# Slave.net
KiCad netlist of a schematic drawn in Altium Designer
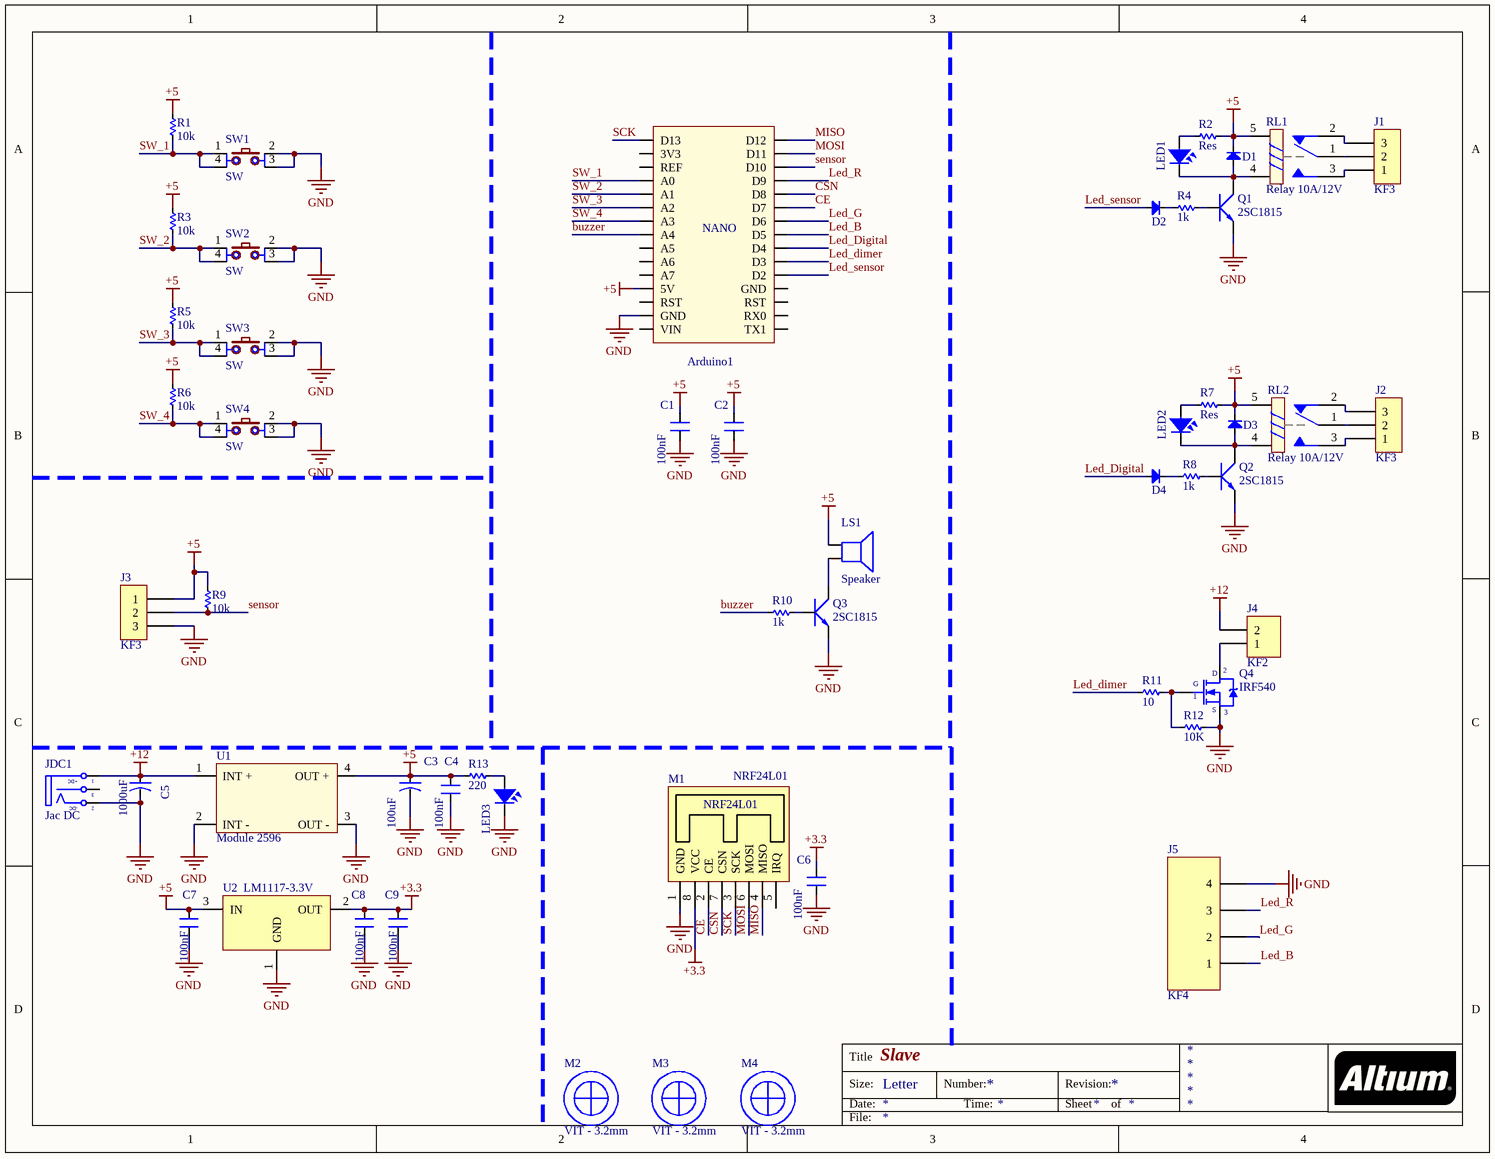
[diagram p0: Slave.SchDoc]

(export (version "E")
  (design (tool "Eeschema 10.0.6"))
  (components
    (comp (ref "Arduino1")
      (value "Arduino Nano")
      (footprint "Arduino Nano")
      (description "Arduino NANO")
      (libsource (lib "thu vien 3d") (part "Arduino Nano"))
    )
    (comp (ref "C1") (value "100nF") (footprint "CN1.5") (libsource (lib "thu vien 3d") (part "CN")))
    (comp (ref "C2") (value "100nF") (footprint "CN1.5") (libsource (lib "thu vien 3d") (part "CN")))
    (comp (ref "C3")
      (value "100uF")
      (footprint "CA-ALU-5")
      (description "Capacitor (Semiconductor SIM Model)")
      (fields (field (name "PUBLISHER") "Altium Limited"))
      (libsource (lib "thu vien 3d") (part "CN-ALU-DIP"))
    )
    (comp (ref "C4") (value "100nF") (footprint "CN1.5") (libsource (lib "thu vien 3d") (part "CN")))
    (comp (ref "C5")
      (value "1000uF")
      (footprint "CA-ALU-6.3")
      (description "Capacitor (Semiconductor SIM Model)")
      (fields (field (name "PUBLISHER") "Altium Limited"))
      (libsource (lib "thu vien 3d") (part "CN-ALU-DIP"))
    )
    (comp (ref "C6") (value "100nF") (footprint "CN1.5") (libsource (lib "thu vien 3d") (part "CN")))
    (comp (ref "C7") (value "100nF") (footprint "CN-SMD-0603") (libsource (lib "thu vien 3d") (part "CN")))
    (comp (ref "C8") (value "100nF") (footprint "CN-SMD-0603") (libsource (lib "thu vien 3d") (part "CN")))
    (comp (ref "C9") (value "100nF") (footprint "CN-SMD-0603") (libsource (lib "thu vien 3d") (part "CN")))
    (comp (ref "D1")
      (value "Diode")
      (footprint "DIO-1A")
      (description "Default Diode")
      (fields (field (name "PUBLISHER") "Altium Limited"))
      (libsource (lib "thu vien 3d") (part "Diode"))
    )
    (comp (ref "D2")
      (value "Diode")
      (footprint "DIO-1A")
      (description "Default Diode")
      (fields (field (name "PUBLISHER") "Altium Limited"))
      (libsource (lib "thu vien 3d") (part "Diode"))
    )
    (comp (ref "D3")
      (value "Diode")
      (footprint "DIO-1A")
      (description "Default Diode")
      (fields (field (name "PUBLISHER") "Altium Limited"))
      (libsource (lib "thu vien 3d") (part "Diode"))
    )
    (comp (ref "D4")
      (value "Diode")
      (footprint "DIO-1A")
      (description "Default Diode")
      (fields (field (name "PUBLISHER") "Altium Limited"))
      (libsource (lib "thu vien 3d") (part "Diode"))
    )
    (comp (ref "J1")
      (value "KF3")
      (footprint "KF3-5.08")
      (fields
        (field (name "MANUFACTURER") "Würth Elektronik eiSos GmbH")
        (field (name "PARTNO") "691103110003")
        (field (name "CREATED BY") "Karrer Zheng")
      )
      (libsource (lib "thu vien 3d") (part "KF3"))
    )
    (comp (ref "J2")
      (value "KF3")
      (footprint "KF3-5.08")
      (fields
        (field (name "MANUFACTURER") "Würth Elektronik eiSos GmbH")
        (field (name "PARTNO") "691103110003")
        (field (name "CREATED BY") "Karrer Zheng")
      )
      (libsource (lib "thu vien 3d") (part "KF3"))
    )
    (comp (ref "J3")
      (value "KF3")
      (footprint "KF3-5.08")
      (fields
        (field (name "MANUFACTURER") "Würth Elektronik eiSos GmbH")
        (field (name "PARTNO") "691103110003")
        (field (name "CREATED BY") "Karrer Zheng")
      )
      (libsource (lib "") (part "KF3_1"))
    )
    (comp (ref "J4")
      (value "KF2")
      (footprint "KF2-5.08")
      (fields
        (field (name "MANUFACTURER") "Würth Elektronik eiSos GmbH")
        (field (name "PARTNO") "691103110002")
        (field (name "CREATED BY") "Karrer Zheng")
      )
      (libsource (lib "thu vien 3d") (part "KF2"))
    )
    (comp (ref "J5")
      (value "KF4")
      (footprint "KF4-5.08")
      (fields
        (field (name "MANUFACTURER") "Würth Elektronik eiSos GmbH")
        (field (name "PARTNO") "691133710004")
        (field (name "CREATED BY") "Baojun Chen")
      )
      (libsource (lib "thu vien 3d") (part "KF4"))
    )
    (comp (ref "JDC1")
      (value "Jac DC")
      (footprint "DC0")
      (description "Jac DC input")
      (libsource (lib "thu vien 3d") (part "DCIN"))
    )
    (comp (ref "LED1")
      (value "LED")
      (footprint "LED-5-Green")
      (description "LED Single colour Green and Red")
      (libsource (lib "thu vien 3d") (part "LED"))
    )
    (comp (ref "LED2")
      (value "LED")
      (footprint "LED-5-Green")
      (description "LED Single colour Green and Red")
      (libsource (lib "thu vien 3d") (part "LED"))
    )
    (comp (ref "LED3")
      (value "LED")
      (footprint "LED-3MM-RED")
      (description "LED Single colour Green and Red")
      (libsource (lib "thu vien 3d") (part "LED"))
    )
    (comp (ref "LS1")
      (value "Speaker")
      (footprint "SPEAKER")
      (description "Loudspeaker")
      (fields (field (name "PUBLISHER") "Altium Limited"))
      (libsource (lib "thu vien 3d") (part "Speaker"))
    )
    (comp (ref "M1")
      (value "NRF24L01")
      (footprint "NRF24L01")
      (libsource (lib "thu vien 3d") (part "NRF24L01"))
    )
    (comp (ref "M2")
      (value "VIT - 3.2mm")
      (footprint "VIT - 3.2MM_2")
      (libsource (lib "Nichietsuvn") (part "VIT - 3.2mm"))
    )
    (comp (ref "M3")
      (value "VIT - 3.2mm")
      (footprint "VIT - 3.2MM_2")
      (libsource (lib "Nichietsuvn") (part "VIT - 3.2mm"))
    )
    (comp (ref "M4")
      (value "VIT - 3.2mm")
      (footprint "VIT - 3.2MM_2")
      (libsource (lib "Nichietsuvn") (part "VIT - 3.2mm"))
    )
    (comp (ref "Q1")
      (value "2SC1815")
      (footprint "TO92-123")
      (description "NPN 600mW, ECB")
      (libsource (lib "thu vien 3d") (part "2SC1815"))
    )
    (comp (ref "Q2")
      (value "2SC1815")
      (footprint "TO92-123")
      (description "NPN 600mW, ECB")
      (libsource (lib "thu vien 3d") (part "2SC1815"))
    )
    (comp (ref "Q3")
      (value "2SC1815")
      (footprint "TO92-123")
      (description "NPN 600mW, ECB")
      (libsource (lib "thu vien 3d") (part "2SC1815"))
    )
    (comp (ref "Q4")
      (value "IRF540")
      (footprint "TO220-123")
      (description "MOSFET N - CHANNEL 500V - 0.75 - 8A - TO-220")
      (libsource (lib "thu vien 3d") (part "IRF840"))
    )
    (comp (ref "R1")
      (value "10k")
      (footprint "RES-1/4W")
      (description "Res")
      (fields
        (field (name "MANUFACTURER") "Generic Components")
        (field (name "PUBLISHER") "Altium Hobart Technology Centre")
      )
      (libsource (lib "thu vien 3d") (part "Res"))
    )
    (comp (ref "R2")
      (value "Res")
      (footprint "RES-1/4W-SMALL")
      (fields
        (field (name "MANUFACTURER") "Generic Components")
        (field (name "PUBLISHER") "Altium Hobart Technology Centre")
      )
      (libsource (lib "thu vien 3d") (part "Res"))
    )
    (comp (ref "R3")
      (value "10k")
      (footprint "RES-1/4W")
      (description "Res")
      (fields
        (field (name "MANUFACTURER") "Generic Components")
        (field (name "PUBLISHER") "Altium Hobart Technology Centre")
      )
      (libsource (lib "thu vien 3d") (part "Res"))
    )
    (comp (ref "R4")
      (value "1k")
      (footprint "RES-1/4W-SMALL")
      (description "Res")
      (fields
        (field (name "MANUFACTURER") "Generic Components")
        (field (name "PUBLISHER") "Altium Hobart Technology Centre")
      )
      (libsource (lib "thu vien 3d") (part "Res"))
    )
    (comp (ref "R5")
      (value "10k")
      (footprint "RES-1/4W")
      (description "Res")
      (fields
        (field (name "MANUFACTURER") "Generic Components")
        (field (name "PUBLISHER") "Altium Hobart Technology Centre")
      )
      (libsource (lib "thu vien 3d") (part "Res"))
    )
    (comp (ref "R6")
      (value "10k")
      (footprint "RES-1/4W")
      (description "Res")
      (fields
        (field (name "MANUFACTURER") "Generic Components")
        (field (name "PUBLISHER") "Altium Hobart Technology Centre")
      )
      (libsource (lib "thu vien 3d") (part "Res"))
    )
    (comp (ref "R7")
      (value "Res")
      (footprint "RES-1/4W-SMALL")
      (fields
        (field (name "MANUFACTURER") "Generic Components")
        (field (name "PUBLISHER") "Altium Hobart Technology Centre")
      )
      (libsource (lib "thu vien 3d") (part "Res"))
    )
    (comp (ref "R8")
      (value "1k")
      (footprint "RES-1/4W-SMALL")
      (description "Res")
      (fields
        (field (name "MANUFACTURER") "Generic Components")
        (field (name "PUBLISHER") "Altium Hobart Technology Centre")
      )
      (libsource (lib "thu vien 3d") (part "Res"))
    )
    (comp (ref "R9")
      (value "10k")
      (footprint "RES-1/4W")
      (description "Res")
      (fields
        (field (name "MANUFACTURER") "Generic Components")
        (field (name "PUBLISHER") "Altium Hobart Technology Centre")
      )
      (libsource (lib "thu vien 3d") (part "Res"))
    )
    (comp (ref "R10")
      (value "1k")
      (footprint "RES-1/4W-SMALL")
      (description "Res")
      (fields
        (field (name "MANUFACTURER") "Generic Components")
        (field (name "PUBLISHER") "Altium Hobart Technology Centre")
      )
      (libsource (lib "thu vien 3d") (part "Res"))
    )
    (comp (ref "R11")
      (value "10")
      (footprint "RES-1/4W-SMALL")
      (description "Res")
      (fields
        (field (name "MANUFACTURER") "Generic Components")
        (field (name "PUBLISHER") "Altium Hobart Technology Centre")
      )
      (libsource (lib "thu vien 3d") (part "Res"))
    )
    (comp (ref "R12")
      (value "10K")
      (footprint "RES-1/4W-SMALL")
      (description "Res")
      (fields
        (field (name "MANUFACTURER") "Generic Components")
        (field (name "PUBLISHER") "Altium Hobart Technology Centre")
      )
      (libsource (lib "thu vien 3d") (part "Res"))
    )
    (comp (ref "R13")
      (value "220")
      (footprint "RES-1/4WD")
      (description "Res")
      (fields
        (field (name "MANUFACTURER") "Generic Components")
        (field (name "PUBLISHER") "Altium Hobart Technology Centre")
      )
      (libsource (lib "thu vien 3d") (part "Res"))
    )
    (comp (ref "RL1")
      (value "Relay 10A/12V")
      (footprint "RELAY 5")
      (description "Relay SPDT,10A - 12VDC 5 Pin")
      (libsource (lib "thu vien 3d") (part "Relay 5"))
    )
    (comp (ref "RL2")
      (value "Relay 10A/12V")
      (footprint "RELAY 5")
      (description "Relay SPDT,10A - 12VDC 5 Pin")
      (libsource (lib "thu vien 3d") (part "Relay 5"))
    )
    (comp (ref "SW1")
      (value "SW")
      (footprint "SW2-DIP")
      (description "Switch button 4 pin")
      (libsource (lib "thu vien 3d") (part "SW4"))
    )
    (comp (ref "SW2")
      (value "SW")
      (footprint "SW2-DIP")
      (description "Switch button 4 pin")
      (libsource (lib "thu vien 3d") (part "SW4"))
    )
    (comp (ref "SW3")
      (value "SW")
      (footprint "SW2-DIP")
      (description "Switch button 4 pin")
      (libsource (lib "thu vien 3d") (part "SW4"))
    )
    (comp (ref "SW4")
      (value "SW")
      (footprint "SW2-DIP")
      (description "Switch button 4 pin")
      (libsource (lib "thu vien 3d") (part "SW4"))
    )
    (comp (ref "U1")
      (value "Module 2596")
      (footprint "Module 2596")
      (libsource (lib "Nichietsuvn") (part "Module 2596"))
    )
    (comp (ref "U2")
      (value "LM1117-3.3V")
      (footprint "SOT223")
      (description "800mA Low-Dropout Linear Regulator")
      (fields (field (name "CREATOR") "Nguyen Ba Bien"))
      (libsource (lib "thu vien 3d") (part "LM1117"))
    )
  )
  (nets
    (net (code "1") (name "+3.3") (class "Default")
      (node (ref "C6") (pin "2") (pinfunction "2_2") (pintype "passive"))
      (node (ref "C8") (pin "2") (pinfunction "2_2") (pintype "passive"))
      (node (ref "C9") (pin "2") (pinfunction "2_2") (pintype "passive"))
      (node (ref "M1") (pin "8") (pinfunction "VCC_8") (pintype "passive"))
      (node (ref "U2") (pin "2") (pinfunction "OUT_2") (pintype "passive"))
    )
    (net (code "2") (name "+5") (class "Default")
      (node (ref "Arduino1") (pin "5V") (pinfunction "5V_5V") (pintype "passive"))
      (node (ref "C1") (pin "2") (pinfunction "2_2") (pintype "passive"))
      (node (ref "C2") (pin "2") (pinfunction "2_2") (pintype "passive"))
      (node (ref "C3") (pin "1") (pinfunction "1_1") (pintype "passive"))
      (node (ref "C4") (pin "2") (pinfunction "2_2") (pintype "passive"))
      (node (ref "C7") (pin "2") (pinfunction "2_2") (pintype "passive"))
      (node (ref "D1") (pin "2") (pinfunction "K_2") (pintype "passive"))
      (node (ref "D3") (pin "2") (pinfunction "K_2") (pintype "passive"))
      (node (ref "J3") (pin "1") (pinfunction "1_1") (pintype "passive"))
      (node (ref "LS1") (pin "1") (pinfunction "1_1") (pintype "passive"))
      (node (ref "R1") (pin "1") (pinfunction "1_1") (pintype "passive"))
      (node (ref "R13") (pin "2") (pinfunction "2_2") (pintype "passive"))
      (node (ref "R2") (pin "1") (pinfunction "1_1") (pintype "passive"))
      (node (ref "R3") (pin "1") (pinfunction "1_1") (pintype "passive"))
      (node (ref "R5") (pin "1") (pinfunction "1_1") (pintype "passive"))
      (node (ref "R6") (pin "1") (pinfunction "1_1") (pintype "passive"))
      (node (ref "R7") (pin "1") (pinfunction "1_1") (pintype "passive"))
      (node (ref "R9") (pin "1") (pinfunction "1_1") (pintype "passive"))
      (node (ref "RL1") (pin "5") (pinfunction "5_5") (pintype "passive"))
      (node (ref "RL2") (pin "5") (pinfunction "5_5") (pintype "passive"))
      (node (ref "U1") (pin "4") (pinfunction "OUT_+_4") (pintype "passive"))
      (node (ref "U2") (pin "3") (pinfunction "IN_3") (pintype "passive"))
    )
    (net (code "3") (name "+12") (class "Default")
      (node (ref "C5") (pin "1") (pinfunction "1_1") (pintype "passive"))
      (node (ref "J4") (pin "2") (pinfunction "2_2") (pintype "passive"))
      (node (ref "JDC1") (pin "1") (pinfunction "T_1") (pintype "passive"))
      (node (ref "U1") (pin "1") (pinfunction "INT_+_1") (pintype "passive"))
    )
    (net (code "4") (name "/CE") (class "Default")
      (node (ref "Arduino1") (pin "D7") (pinfunction "D7_D7") (pintype "passive"))
      (node (ref "M1") (pin "2") (pinfunction "CE_2") (pintype "passive"))
    )
    (net (code "5") (name "/CSN") (class "Default")
      (node (ref "Arduino1") (pin "D8") (pinfunction "D8_D8") (pintype "passive"))
      (node (ref "M1") (pin "7") (pinfunction "CSN_7") (pintype "passive"))
    )
    (net (code "6") (name "/Led_B") (class "Default")
      (node (ref "Arduino1") (pin "D5") (pinfunction "D5_D5") (pintype "passive"))
      (node (ref "J5") (pin "1") (pinfunction "1_1") (pintype "passive"))
    )
    (net (code "7") (name "/Led_Digital") (class "Default")
      (node (ref "Arduino1") (pin "D4") (pinfunction "D4_D4") (pintype "passive"))
      (node (ref "D4") (pin "1") (pinfunction "A_1") (pintype "passive"))
    )
    (net (code "8") (name "/Led_G") (class "Default")
      (node (ref "Arduino1") (pin "D6") (pinfunction "D6_D6") (pintype "passive"))
      (node (ref "J5") (pin "2") (pinfunction "2_2") (pintype "passive"))
    )
    (net (code "9") (name "/Led_R") (class "Default")
      (node (ref "Arduino1") (pin "D9") (pinfunction "D9_D9") (pintype "passive"))
      (node (ref "J5") (pin "3") (pinfunction "3_3") (pintype "passive"))
    )
    (net (code "10") (name "/Led_dimer") (class "Default")
      (node (ref "Arduino1") (pin "D3") (pinfunction "D3_D3") (pintype "passive"))
      (node (ref "R11") (pin "2") (pinfunction "2_2") (pintype "passive"))
    )
    (net (code "11") (name "/Led_sensor") (class "Default")
      (node (ref "Arduino1") (pin "D2") (pinfunction "D2_D2") (pintype "passive"))
      (node (ref "D2") (pin "1") (pinfunction "A_1") (pintype "passive"))
    )
    (net (code "12") (name "/MISO") (class "Default")
      (node (ref "Arduino1") (pin "D12") (pinfunction "D12_D12") (pintype "passive"))
      (node (ref "M1") (pin "4") (pinfunction "MISO_4") (pintype "passive"))
    )
    (net (code "13") (name "/MOSI") (class "Default")
      (node (ref "Arduino1") (pin "D11") (pinfunction "D11_D11") (pintype "passive"))
      (node (ref "M1") (pin "6") (pinfunction "MOSI_6") (pintype "passive"))
    )
    (net (code "14") (name "/SCK") (class "Default")
      (node (ref "Arduino1") (pin "D13") (pinfunction "D13_D13") (pintype "passive"))
      (node (ref "M1") (pin "3") (pinfunction "SCK_3") (pintype "passive"))
    )
    (net (code "15") (name "/SW_1") (class "Default")
      (node (ref "Arduino1") (pin "A0") (pinfunction "A0_A0") (pintype "passive"))
      (node (ref "R1") (pin "2") (pinfunction "2_2") (pintype "passive"))
      (node (ref "SW1") (pin "1") (pintype "passive"))
      (node (ref "SW1") (pin "4") (pinfunction "4_4") (pintype "passive"))
    )
    (net (code "16") (name "/SW_2") (class "Default")
      (node (ref "Arduino1") (pin "A1") (pinfunction "A1_A1") (pintype "passive"))
      (node (ref "R3") (pin "2") (pinfunction "2_2") (pintype "passive"))
      (node (ref "SW2") (pin "1") (pintype "passive"))
      (node (ref "SW2") (pin "4") (pinfunction "4_4") (pintype "passive"))
    )
    (net (code "17") (name "/SW_3") (class "Default")
      (node (ref "Arduino1") (pin "A2") (pinfunction "A2_A2") (pintype "passive"))
      (node (ref "R5") (pin "2") (pinfunction "2_2") (pintype "passive"))
      (node (ref "SW3") (pin "1") (pintype "passive"))
      (node (ref "SW3") (pin "4") (pinfunction "4_4") (pintype "passive"))
    )
    (net (code "18") (name "/SW_4") (class "Default")
      (node (ref "Arduino1") (pin "A3") (pinfunction "A3_A3") (pintype "passive"))
      (node (ref "R6") (pin "2") (pinfunction "2_2") (pintype "passive"))
      (node (ref "SW4") (pin "1") (pintype "passive"))
      (node (ref "SW4") (pin "4") (pinfunction "4_4") (pintype "passive"))
    )
    (net (code "19") (name "/buzzer") (class "Default")
      (node (ref "Arduino1") (pin "A4") (pinfunction "A4_A4") (pintype "passive"))
      (node (ref "R10") (pin "2") (pinfunction "2_2") (pintype "passive"))
    )
    (net (code "20") (name "/sensor") (class "Default")
      (node (ref "Arduino1") (pin "D10") (pinfunction "D10_D10") (pintype "passive"))
      (node (ref "J3") (pin "2") (pinfunction "2_2") (pintype "passive"))
      (node (ref "R9") (pin "2") (pinfunction "2_2") (pintype "passive"))
    )
    (net (code "21") (name "GND") (class "Default")
      (node (ref "Arduino1") (pin "GND") (pinfunction "GND_GND") (pintype "passive"))
      (node (ref "C1") (pin "1") (pinfunction "1_1") (pintype "passive"))
      (node (ref "C2") (pin "1") (pinfunction "1_1") (pintype "passive"))
      (node (ref "C3") (pin "2") (pinfunction "2_2") (pintype "passive"))
      (node (ref "C4") (pin "1") (pinfunction "1_1") (pintype "passive"))
      (node (ref "C5") (pin "2") (pinfunction "2_2") (pintype "passive"))
      (node (ref "C6") (pin "1") (pinfunction "1_1") (pintype "passive"))
      (node (ref "C7") (pin "1") (pinfunction "1_1") (pintype "passive"))
      (node (ref "C8") (pin "1") (pinfunction "1_1") (pintype "passive"))
      (node (ref "C9") (pin "1") (pinfunction "1_1") (pintype "passive"))
      (node (ref "J3") (pin "3") (pinfunction "3_3") (pintype "passive"))
      (node (ref "J5") (pin "4") (pinfunction "4_4") (pintype "passive"))
      (node (ref "JDC1") (pin "2") (pinfunction "TN_2") (pintype "passive"))
      (node (ref "LED3") (pin "2") (pinfunction "2_2") (pintype "passive"))
      (node (ref "M1") (pin "1") (pinfunction "GND_1") (pintype "passive"))
      (node (ref "Q1") (pin "1") (pinfunction "E_1") (pintype "passive"))
      (node (ref "Q2") (pin "1") (pinfunction "E_1") (pintype "passive"))
      (node (ref "Q3") (pin "1") (pinfunction "E_1") (pintype "passive"))
      (node (ref "Q4") (pin "3") (pinfunction "S_3") (pintype "passive"))
      (node (ref "R12") (pin "1") (pinfunction "1_1") (pintype "passive"))
      (node (ref "SW1") (pin "2") (pinfunction "2_2") (pintype "passive"))
      (node (ref "SW1") (pin "3") (pinfunction "3_3") (pintype "passive"))
      (node (ref "SW2") (pin "2") (pinfunction "2_2") (pintype "passive"))
      (node (ref "SW2") (pin "3") (pinfunction "3_3") (pintype "passive"))
      (node (ref "SW3") (pin "2") (pinfunction "2_2") (pintype "passive"))
      (node (ref "SW3") (pin "3") (pinfunction "3_3") (pintype "passive"))
      (node (ref "SW4") (pin "2") (pinfunction "2_2") (pintype "passive"))
      (node (ref "SW4") (pin "3") (pinfunction "3_3") (pintype "passive"))
      (node (ref "U1") (pin "2") (pinfunction "INT_-_2") (pintype "passive"))
      (node (ref "U1") (pin "3") (pinfunction "OUT_-_3") (pintype "passive"))
      (node (ref "U2") (pin "1") (pinfunction "GND_1") (pintype "passive"))
    )
    (net (code "22") (name "Net-(D1-A)") (class "Default")
      (node (ref "D1") (pin "1") (pinfunction "A_1") (pintype "passive"))
      (node (ref "LED1") (pin "2") (pinfunction "2_2") (pintype "passive"))
      (node (ref "Q1") (pin "2") (pinfunction "C_2") (pintype "passive"))
      (node (ref "RL1") (pin "4") (pinfunction "4_4") (pintype "passive"))
    )
    (net (code "23") (name "Net-(D2-K)") (class "Default")
      (node (ref "D2") (pin "2") (pinfunction "K_2") (pintype "passive"))
      (node (ref "R4") (pin "2") (pinfunction "2_2") (pintype "passive"))
    )
    (net (code "24") (name "Net-(D3-A)") (class "Default")
      (node (ref "D3") (pin "1") (pinfunction "A_1") (pintype "passive"))
      (node (ref "LED2") (pin "2") (pinfunction "2_2") (pintype "passive"))
      (node (ref "Q2") (pin "2") (pinfunction "C_2") (pintype "passive"))
      (node (ref "RL2") (pin "4") (pinfunction "4_4") (pintype "passive"))
    )
    (net (code "25") (name "Net-(D4-K)") (class "Default")
      (node (ref "D4") (pin "2") (pinfunction "K_2") (pintype "passive"))
      (node (ref "R8") (pin "2") (pinfunction "2_2") (pintype "passive"))
    )
    (net (code "26") (name "Net-(J1-Pad1)") (class "Default")
      (node (ref "J1") (pin "1") (pinfunction "1_1") (pintype "passive"))
      (node (ref "RL1") (pin "3") (pinfunction "3_3") (pintype "passive"))
    )
    (net (code "27") (name "Net-(J1-Pad2)") (class "Default")
      (node (ref "J1") (pin "2") (pinfunction "2_2") (pintype "passive"))
      (node (ref "RL1") (pin "1") (pinfunction "1_1") (pintype "passive"))
    )
    (net (code "28") (name "Net-(J1-Pad3)") (class "Default")
      (node (ref "J1") (pin "3") (pinfunction "3_3") (pintype "passive"))
      (node (ref "RL1") (pin "2") (pinfunction "2_2") (pintype "passive"))
    )
    (net (code "29") (name "Net-(J2-Pad1)") (class "Default")
      (node (ref "J2") (pin "1") (pinfunction "1_1") (pintype "passive"))
      (node (ref "RL2") (pin "3") (pinfunction "3_3") (pintype "passive"))
    )
    (net (code "30") (name "Net-(J2-Pad2)") (class "Default")
      (node (ref "J2") (pin "2") (pinfunction "2_2") (pintype "passive"))
      (node (ref "RL2") (pin "1") (pinfunction "1_1") (pintype "passive"))
    )
    (net (code "31") (name "Net-(J2-Pad3)") (class "Default")
      (node (ref "J2") (pin "3") (pinfunction "3_3") (pintype "passive"))
      (node (ref "RL2") (pin "2") (pinfunction "2_2") (pintype "passive"))
    )
    (net (code "32") (name "Net-(LED1-Pad1)") (class "Default")
      (node (ref "LED1") (pin "1") (pinfunction "1_1") (pintype "passive"))
      (node (ref "R2") (pin "2") (pinfunction "2_2") (pintype "passive"))
    )
    (net (code "33") (name "Net-(LED2-Pad1)") (class "Default")
      (node (ref "LED2") (pin "1") (pinfunction "1_1") (pintype "passive"))
      (node (ref "R7") (pin "2") (pinfunction "2_2") (pintype "passive"))
    )
    (net (code "34") (name "Net-(LED3-Pad1)") (class "Default")
      (node (ref "LED3") (pin "1") (pinfunction "1_1") (pintype "passive"))
      (node (ref "R13") (pin "1") (pinfunction "1_1") (pintype "passive"))
    )
    (net (code "35") (name "Net-(Q1-B)") (class "Default")
      (node (ref "Q1") (pin "3") (pinfunction "B_3") (pintype "passive"))
      (node (ref "R4") (pin "1") (pinfunction "1_1") (pintype "passive"))
    )
    (net (code "36") (name "Net-(Q2-B)") (class "Default")
      (node (ref "Q2") (pin "3") (pinfunction "B_3") (pintype "passive"))
      (node (ref "R8") (pin "1") (pinfunction "1_1") (pintype "passive"))
    )
    (net (code "37") (name "Net-(Q3-B)") (class "Default")
      (node (ref "Q3") (pin "3") (pinfunction "B_3") (pintype "passive"))
      (node (ref "R10") (pin "1") (pinfunction "1_1") (pintype "passive"))
    )
    (net (code "38") (name "Net-(Q3-C)") (class "Default")
      (node (ref "LS1") (pin "2") (pinfunction "2_2") (pintype "passive"))
      (node (ref "Q3") (pin "2") (pinfunction "C_2") (pintype "passive"))
    )
    (net (code "39") (name "Net-(Q4-D)") (class "Default")
      (node (ref "J4") (pin "1") (pinfunction "1_1") (pintype "passive"))
      (node (ref "Q4") (pin "2") (pinfunction "D_2") (pintype "passive"))
    )
    (net (code "40") (name "Net-(Q4-G)") (class "Default")
      (node (ref "Q4") (pin "1") (pinfunction "G_1") (pintype "passive"))
      (node (ref "R11") (pin "1") (pinfunction "1_1") (pintype "passive"))
      (node (ref "R12") (pin "2") (pinfunction "2_2") (pintype "passive"))
    )
    (net (code "41") (name "unconnected-(Arduino1-Pad3V3)") (class "Default")
      (node (ref "Arduino1") (pin "3V3") (pinfunction "3V3_3V3") (pintype "passive"))
    )
    (net (code "42") (name "unconnected-(Arduino1-PadA5)") (class "Default")
      (node (ref "Arduino1") (pin "A5") (pinfunction "A5_A5") (pintype "passive"))
    )
    (net (code "43") (name "unconnected-(Arduino1-PadA6)") (class "Default")
      (node (ref "Arduino1") (pin "A6") (pinfunction "A6_A6") (pintype "passive"))
    )
    (net (code "44") (name "unconnected-(Arduino1-PadA7)") (class "Default")
      (node (ref "Arduino1") (pin "A7") (pinfunction "A7_A7") (pintype "passive"))
    )
    (net (code "45") (name "unconnected-(Arduino1-PadGND)") (class "Default")
      (node (ref "Arduino1") (pin "GND") (pinfunction "GND_GND") (pintype "passive"))
    )
    (net (code "46") (name "unconnected-(Arduino1-PadREF)") (class "Default")
      (node (ref "Arduino1") (pin "REF") (pinfunction "REF_REF") (pintype "passive"))
    )
    (net (code "47") (name "unconnected-(Arduino1-PadRST)") (class "Default")
      (node (ref "Arduino1") (pin "RST") (pinfunction "RST_RST") (pintype "passive"))
    )
    (net (code "48") (name "unconnected-(Arduino1-PadRST)_1") (class "Default")
      (node (ref "Arduino1") (pin "RST") (pinfunction "RST_RST") (pintype "passive"))
    )
    (net (code "49") (name "unconnected-(Arduino1-PadRX0)") (class "Default")
      (node (ref "Arduino1") (pin "RX0") (pinfunction "RX0_RX0") (pintype "passive"))
    )
    (net (code "50") (name "unconnected-(Arduino1-PadTX1)") (class "Default")
      (node (ref "Arduino1") (pin "TX1") (pinfunction "TX1_TX1") (pintype "passive"))
    )
    (net (code "51") (name "unconnected-(Arduino1-PadVIN)") (class "Default")
      (node (ref "Arduino1") (pin "VIN") (pinfunction "VIN_VIN") (pintype "passive"))
    )
    (net (code "52") (name "unconnected-(JDC1-S-Pad3)") (class "Default")
      (node (ref "JDC1") (pin "3") (pinfunction "S_3") (pintype "power_in"))
    )
    (net (code "53") (name "unconnected-(M1-IRQ-Pad5)") (class "Default")
      (node (ref "M1") (pin "5") (pinfunction "IRQ_5") (pintype "passive"))
    )
  )
)
